# DCSupplyHub.net
KiCad netlist of a schematic drawn in Altium Designer
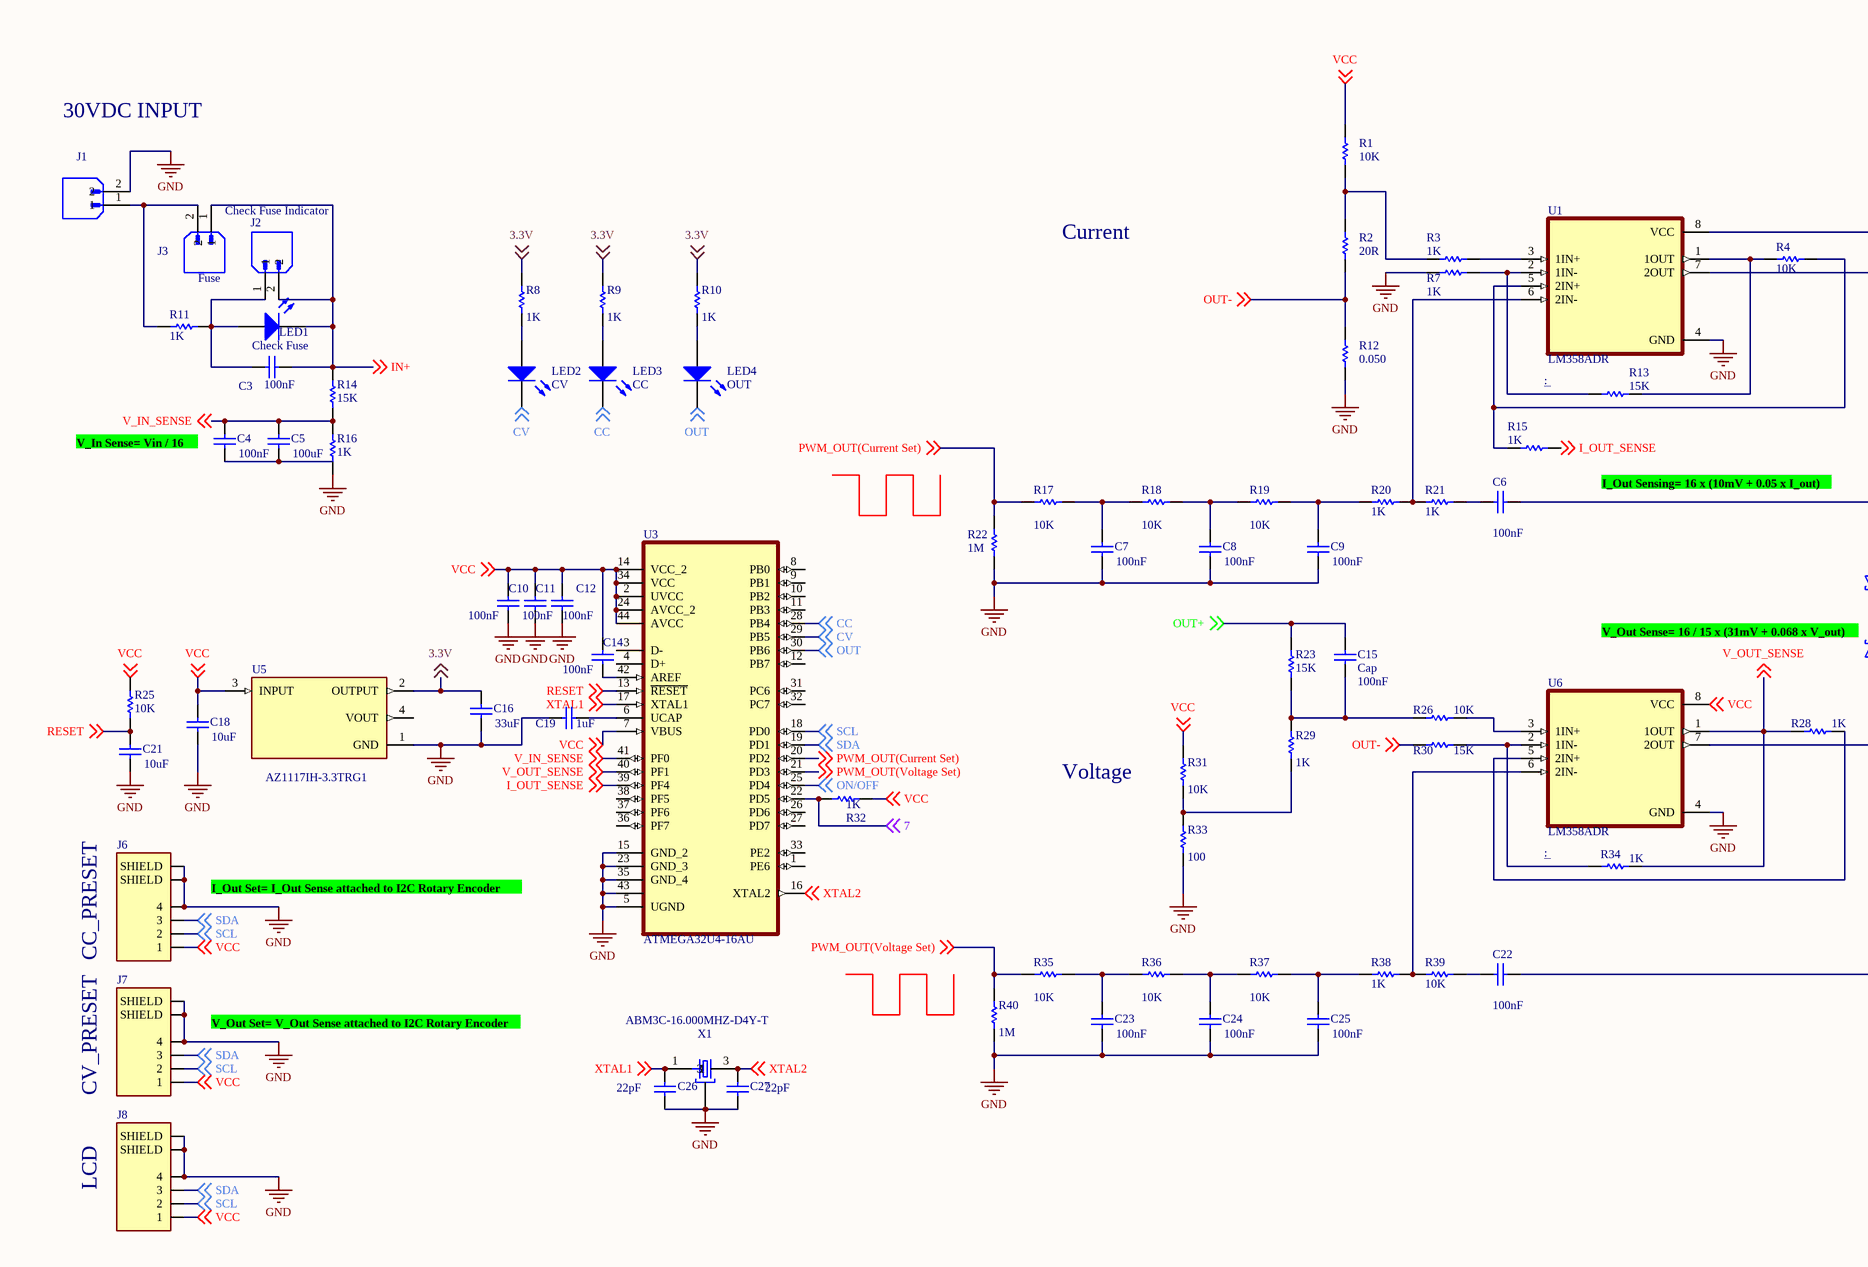
[diagram p0: DCSupplyHub.SchDoc, left]
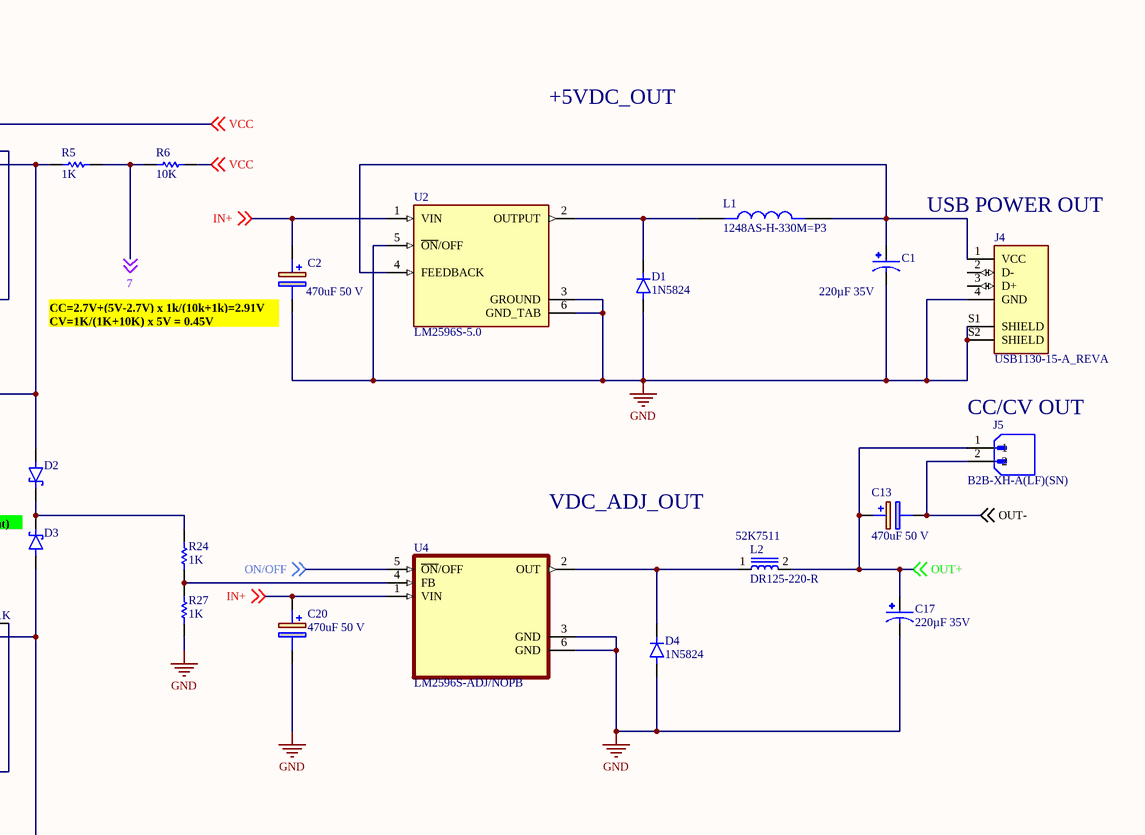
[diagram p1: DCSupplyHub.SchDoc, right]

(export (version "E")
  (design (tool "Eeschema 10.0.6"))
  (components
    (comp (ref "C1")
      (value "EEEFP1V221AP")
      (footprint "CAP_EEEFP1V221AP")
      (description "220ÂµF 35V Aluminum Electrolytic Capacitors Radial, Can - SMD 80mOhm @ 100kHz 2000 Hrs @ 105Â°C")
      (fields
        (field (name "MP") "EEE-FP1V221AP")
        (field (name "MF") "Panasonic Electronic")
        (field (name "PARAMETER 1") "220µF 35V")
      )
      (libsource (lib "cc cv power supply") (part "EEEFP1V221AP"))
    )
    (comp (ref "C2")
      (value "470uF 50 V")
      (footprint "CAPAE1710X1700N")
      (fields
        (field (name "MANUFACTURER_PART_NUMBER") "865060663013")
        (field (name "MOUSER PART NUMBER") "710-865060663013")
      )
      (libsource (lib "cc cv power supply") (part "865060663013"))
    )
    (comp (ref "C3")
      (value "100nF")
      (footprint "CAPC3216X110N")
      (description "Capacitor")
      (fields (field (name "Comment") "Cap") (field (name "PUBLISHER") "Altium Limited"))
      (libsource (lib "cc cv power supply") (part "Cap"))
    )
    (comp (ref "C4")
      (value "100nF")
      (footprint "CAPC3216X110N")
      (description "Capacitor")
      (fields (field (name "Comment") "Cap") (field (name "PUBLISHER") "Altium Limited"))
      (libsource (lib "cc cv power supply") (part "Cap"))
    )
    (comp (ref "C5")
      (value "100uF")
      (footprint "CAPC3216X110N")
      (description "Capacitor")
      (fields (field (name "Comment") "Cap") (field (name "PUBLISHER") "Altium Limited"))
      (libsource (lib "cc cv power supply") (part "Cap"))
    )
    (comp (ref "C6")
      (value "100nF")
      (footprint "CAPC3216X110N")
      (description "Capacitor")
      (fields (field (name "Comment") "Cap") (field (name "PUBLISHER") "Altium Limited"))
      (libsource (lib "cc cv power supply") (part "Cap"))
    )
    (comp (ref "C7")
      (value "100nF")
      (footprint "CAPC3216X110N")
      (description "Capacitor")
      (fields (field (name "Comment") "Cap") (field (name "PUBLISHER") "Altium Limited"))
      (libsource (lib "cc cv power supply") (part "Cap"))
    )
    (comp (ref "C8")
      (value "100nF")
      (footprint "CAPC3216X110N")
      (description "Capacitor")
      (fields (field (name "Comment") "Cap") (field (name "PUBLISHER") "Altium Limited"))
      (libsource (lib "cc cv power supply") (part "Cap"))
    )
    (comp (ref "C9")
      (value "100nF")
      (footprint "CAPC3216X110N")
      (description "Capacitor")
      (fields (field (name "Comment") "Cap") (field (name "PUBLISHER") "Altium Limited"))
      (libsource (lib "cc cv power supply") (part "Cap"))
    )
    (comp (ref "C10")
      (value "100nF")
      (footprint "CAPC3216X110N")
      (description "Capacitor")
      (fields (field (name "Comment") "Cap") (field (name "PUBLISHER") "Altium Limited"))
      (libsource (lib "cc cv power supply") (part "Cap"))
    )
    (comp (ref "C11")
      (value "100nF")
      (footprint "CAPC3216X110N")
      (description "Capacitor")
      (fields (field (name "Comment") "Cap") (field (name "PUBLISHER") "Altium Limited"))
      (libsource (lib "cc cv power supply") (part "Cap"))
    )
    (comp (ref "C12")
      (value "100nF")
      (footprint "CAPC3216X110N")
      (description "Capacitor")
      (fields (field (name "Comment") "Cap") (field (name "PUBLISHER") "Altium Limited"))
      (libsource (lib "cc cv power supply") (part "Cap"))
    )
    (comp (ref "C13")
      (value "470uF 50 V")
      (footprint "CAPAE1710X1700N")
      (fields
        (field (name "MANUFACTURER_PART_NUMBER") "865060663013")
        (field (name "MOUSER PART NUMBER") "710-865060663013")
      )
      (libsource (lib "") (part "865060663013_1"))
    )
    (comp (ref "C14")
      (value "100nF")
      (footprint "CAPC3216X110N")
      (description "Capacitor")
      (fields (field (name "Comment") "Cap") (field (name "PUBLISHER") "Altium Limited"))
      (libsource (lib "Miscellaneous Devices") (part "Cap"))
    )
    (comp (ref "C15")
      (value "Cap")
      (footprint "CAPC3216X110N")
      (description "Capacitor")
      (fields (field (name "ALTIUM_VALUE") "100nF") (field (name "PUBLISHER") "Altium Limited"))
      (libsource (lib "cc cv power supply") (part "Cap"))
    )
    (comp (ref "C16")
      (value "33uF")
      (footprint "CAPC3216X110N")
      (description "Capacitor")
      (fields (field (name "Comment") "Cap") (field (name "PUBLISHER") "Altium Limited"))
      (libsource (lib "cc cv power supply") (part "Cap"))
    )
    (comp (ref "C17")
      (value "EEEFP1V221AP")
      (footprint "CAP_EEEFP1V221AP")
      (description "220ÂµF 35V Aluminum Electrolytic Capacitors Radial, Can - SMD 80mOhm @ 100kHz 2000 Hrs @ 105Â°C")
      (fields
        (field (name "MP") "EEE-FP1V221AP")
        (field (name "MF") "Panasonic Electronic")
        (field (name "PARAMETER 1") "220µF 35V")
      )
      (libsource (lib "cc cv power supply") (part "EEEFP1V221AP"))
    )
    (comp (ref "C18")
      (value "10uF")
      (footprint "CAPC3216X110N")
      (description "Capacitor")
      (fields (field (name "Comment") "Cap") (field (name "PUBLISHER") "Altium Limited"))
      (libsource (lib "cc cv power supply") (part "Cap"))
    )
    (comp (ref "C19")
      (value "1uF")
      (footprint "CAPC3216X110N")
      (description "Capacitor")
      (fields (field (name "Comment") "Cap") (field (name "PUBLISHER") "Altium Limited"))
      (libsource (lib "cc cv power supply") (part "Cap"))
    )
    (comp (ref "C20")
      (value "470uF 50 V")
      (footprint "CAPAE1710X1700N")
      (fields
        (field (name "MANUFACTURER_PART_NUMBER") "865060663013")
        (field (name "MOUSER PART NUMBER") "710-865060663013")
      )
      (libsource (lib "cc cv power supply") (part "865060663013"))
    )
    (comp (ref "C21")
      (value "10uF")
      (footprint "CAPC3216X110N")
      (description "Capacitor")
      (fields (field (name "Comment") "Cap") (field (name "PUBLISHER") "Altium Limited"))
      (libsource (lib "cc cv power supply") (part "Cap"))
    )
    (comp (ref "C22")
      (value "100nF")
      (footprint "CAPC3216X110N")
      (description "Capacitor")
      (fields (field (name "Comment") "Cap") (field (name "PUBLISHER") "Altium Limited"))
      (libsource (lib "cc cv power supply") (part "Cap"))
    )
    (comp (ref "C23")
      (value "100nF")
      (footprint "CAPC3216X110N")
      (description "Capacitor")
      (fields (field (name "Comment") "Cap") (field (name "PUBLISHER") "Altium Limited"))
      (libsource (lib "cc cv power supply") (part "Cap"))
    )
    (comp (ref "C24")
      (value "100nF")
      (footprint "CAPC3216X110N")
      (description "Capacitor")
      (fields (field (name "Comment") "Cap") (field (name "PUBLISHER") "Altium Limited"))
      (libsource (lib "cc cv power supply") (part "Cap"))
    )
    (comp (ref "C25")
      (value "100nF")
      (footprint "CAPC3216X110N")
      (description "Capacitor")
      (fields (field (name "Comment") "Cap") (field (name "PUBLISHER") "Altium Limited"))
      (libsource (lib "cc cv power supply") (part "Cap"))
    )
    (comp (ref "C26")
      (value "22pF")
      (footprint "CAPC3216X110N")
      (description "Capacitor")
      (fields (field (name "Comment") "Cap") (field (name "PUBLISHER") "Altium Limited"))
      (libsource (lib "cc cv power supply") (part "Cap"))
    )
    (comp (ref "C27")
      (value "22pF")
      (footprint "CAPC3216X110N")
      (description "Capacitor")
      (fields (field (name "Comment") "Cap") (field (name "PUBLISHER") "Altium Limited"))
      (libsource (lib "cc cv power supply") (part "Cap"))
    )
    (comp (ref "D1")
      (value "1N5824")
      (footprint "DIOAD1898W129L762D1143")
      (description "Diode Schottky 30V 5A Through Hole Axial")
      (fields (field (name "MF") "Microsemi Corporation"))
      (libsource (lib "cc cv power supply") (part "1N5824"))
    )
    (comp (ref "D2")
      (value "SD1206S020S1R0")
      (footprint "DIOSC190X340X116-2N")
      (description "Diode Schottky 20 V 1A (DC) Surface Mount 1206 (3216 Metric)")
      (fields (field (name "MF") "AVX"))
      (libsource (lib "cc cv power supply") (part "SD1206S020S1R0"))
    )
    (comp (ref "D3")
      (value "SD1206S020S1R0")
      (footprint "DIOSC190X340X116-2N")
      (description "Diode Schottky 20 V 1A (DC) Surface Mount 1206 (3216 Metric)")
      (fields (field (name "MF") "AVX"))
      (libsource (lib "cc cv power supply") (part "SD1206S020S1R0"))
    )
    (comp (ref "D4")
      (value "1N5824")
      (footprint "DIOAD1898W129L762D1143")
      (description "Diode Schottky 30V 5A Through Hole Axial")
      (fields (field (name "MF") "Microsemi Corporation"))
      (libsource (lib "cc cv power supply") (part "1N5824"))
    )
    (comp (ref "J1")
      (value "B2B-XH-A(LF)(SN)")
      (footprint "JST_B2B-XH-A(LF)(SN)")
      (description "Connector Header Through Hole 2 position 0.098 (2.50mm)")
      (fields (field (name "MF") "JST Sales"))
      (libsource (lib "") (part "B2B-XH-A(LF)(SN)_3"))
    )
    (comp (ref "J2")
      (value "Check Fuse Indicator")
      (footprint "JST_B2B-XH-A(LF)(SN)")
      (description "Connector Header Through Hole 2 position 0.098 (2.50mm)")
      (fields (field (name "MF") "JST Sales") (field (name "MP") "B2B-XH-A(LF)(SN)"))
      (libsource (lib "cc cv power supply") (part "B2B-XH-A(LF)(SN)"))
    )
    (comp (ref "J3")
      (value "Fuse")
      (footprint "JST_B2B-XH-A(LF)(SN)")
      (description "Connector Header Through Hole 2 position 0.098 (2.50mm)")
      (fields (field (name "MF") "JST Sales") (field (name "MP") "B2B-XH-A(LF)(SN)"))
      (libsource (lib "") (part "B2B-XH-A(LF)(SN)_2"))
    )
    (comp (ref "J4")
      (value "USB1130-15-A_REVA")
      (footprint "GCT_USB1130-15-A_REVA")
      (fields (field (name "MP") "USB1130-15-A") (field (name "MF") "Global Connector Technology"))
      (libsource (lib "cc cv power supply") (part "USB1130-15-A_REVA"))
    )
    (comp (ref "J5")
      (value "B2B-XH-A(LF)(SN)")
      (footprint "JST_B2B-XH-A(LF)(SN)")
      (description "Connector Header Through Hole 2 position 0.098 (2.50mm)")
      (fields (field (name "MF") "JST Sales"))
      (libsource (lib "") (part "B2B-XH-A(LF)(SN)_1"))
    )
    (comp (ref "J6")
      (value "CC_PRESET")
      (footprint "JST_SM04B-SRSS-TB(LF)(SN)")
      (description "SH Series 1.0 mm Pitch 2 Position Single Row Side Entry Shrouded Header")
      (fields (field (name "MP") "SM04B-SRSS-TB(LF)(SN)"))
      (libsource (lib "cc cv power supply") (part "SM04B-SRSS-TB(LF)(SN)"))
    )
    (comp (ref "J7")
      (value "CV_PRESET")
      (footprint "JST_SM04B-SRSS-TB(LF)(SN)")
      (description "SH Series 1.0 mm Pitch 2 Position Single Row Side Entry Shrouded Header")
      (fields (field (name "MP") "SM04B-SRSS-TB(LF)(SN)"))
      (libsource (lib "cc cv power supply") (part "SM04B-SRSS-TB(LF)(SN)"))
    )
    (comp (ref "J8")
      (value "LCD")
      (footprint "JST_SM04B-SRSS-TB(LF)(SN)")
      (description "SH Series 1.0 mm Pitch 2 Position Single Row Side Entry Shrouded Header")
      (fields (field (name "MP") "SM04B-SRSS-TB(LF)(SN)"))
      (libsource (lib "cc cv power supply") (part "SM04B-SRSS-TB(LF)(SN)"))
    )
    (comp (ref "L1")
      (value "1248AS-H-330M=P3")
      (footprint "IND_1248AS-H-330M=P3")
      (description "Inductor with Inductance: 33uH Tol. +/-20%, Package: 3131 _8080_")
      (fields (field (name "MF") "Murata") (field (name "DIGI-KEY_PART_NUMBER") "490-10797-1-ND"))
      (libsource (lib "cc cv power supply") (part "1248AS-H-330M=P3"))
    )
    (comp (ref "L2")
      (value "DR125-220-R")
      (footprint "INDM1250X1250X600")
      (description "Inductor Power Shielded Drum Core 3.084u(OCL)H/3.3uH 20% 100KHz Ferrite 9.26A 6.3mOhm DCR T/R")
      (fields (field (name "SUPPLIER PART NUMBER 1") "52K7511"))
      (libsource (lib "cc cv power supply") (part "DR125-220-R"))
    )
    (comp (ref "LED1")
      (value "Check Fuse")
      (footprint "3.2X1.6X1.1")
      (description "Typical RED, GREEN, YELLOW, AMBER GaAs LED")
      (fields (field (name "PUBLISHER") "Altium Limited"))
      (libsource (lib "cc cv power supply") (part "LED2"))
    )
    (comp (ref "LED2")
      (value "CV")
      (footprint "3.2X1.6X1.1")
      (description "Typical RED, GREEN, YELLOW, AMBER GaAs LED")
      (fields (field (name "PUBLISHER") "Altium Limited"))
      (libsource (lib "cc cv power supply") (part "LED2"))
    )
    (comp (ref "LED3")
      (value "CC")
      (footprint "3.2X1.6X1.1")
      (description "Typical RED, GREEN, YELLOW, AMBER GaAs LED")
      (fields (field (name "PUBLISHER") "Altium Limited"))
      (libsource (lib "cc cv power supply") (part "LED2"))
    )
    (comp (ref "LED4")
      (value "OUT")
      (footprint "3.2X1.6X1.1")
      (description "Typical RED, GREEN, YELLOW, AMBER GaAs LED")
      (fields (field (name "PUBLISHER") "Altium Limited"))
      (libsource (lib "cc cv power supply") (part "LED2"))
    )
    (comp (ref "R1")
      (value "10K")
      (footprint "RESC3116X60N")
      (description "Resistor")
      (fields (field (name "Comment") "Res1") (field (name "PUBLISHER") "Altium Limited"))
      (libsource (lib "cc cv power supply") (part "Res1"))
    )
    (comp (ref "R2")
      (value "20R")
      (footprint "RESC3116X60N")
      (description "Resistor")
      (fields (field (name "Comment") "Res1") (field (name "PUBLISHER") "Altium Limited"))
      (libsource (lib "cc cv power supply") (part "Res1"))
    )
    (comp (ref "R3")
      (value "1K")
      (footprint "RESC3116X60N")
      (description "Resistor")
      (fields (field (name "Comment") "Res1") (field (name "PUBLISHER") "Altium Limited"))
      (libsource (lib "cc cv power supply") (part "Res1"))
    )
    (comp (ref "R4")
      (value "10K")
      (footprint "RESC3116X60N")
      (description "Resistor")
      (fields (field (name "Comment") "Res1") (field (name "PUBLISHER") "Altium Limited"))
      (libsource (lib "cc cv power supply") (part "Res1"))
    )
    (comp (ref "R5")
      (value "1K")
      (footprint "RESC3116X60N")
      (description "Resistor")
      (fields (field (name "Comment") "Res1") (field (name "PUBLISHER") "Altium Limited"))
      (libsource (lib "cc cv power supply") (part "Res1"))
    )
    (comp (ref "R6")
      (value "10K")
      (footprint "RESC3116X60N")
      (description "Resistor")
      (fields (field (name "Comment") "Res1") (field (name "PUBLISHER") "Altium Limited"))
      (libsource (lib "cc cv power supply") (part "Res1"))
    )
    (comp (ref "R7")
      (value "1K")
      (footprint "RESC3116X60N")
      (description "Resistor")
      (fields (field (name "Comment") "Res1") (field (name "PUBLISHER") "Altium Limited"))
      (libsource (lib "cc cv power supply") (part "Res1"))
    )
    (comp (ref "R8")
      (value "1K")
      (footprint "RESC3116X60N")
      (description "Resistor")
      (fields (field (name "Comment") "Res1") (field (name "PUBLISHER") "Altium Limited"))
      (libsource (lib "cc cv power supply") (part "Res1"))
    )
    (comp (ref "R9")
      (value "1K")
      (footprint "RESC3116X60N")
      (description "Resistor")
      (fields (field (name "Comment") "Res1") (field (name "PUBLISHER") "Altium Limited"))
      (libsource (lib "cc cv power supply") (part "Res1"))
    )
    (comp (ref "R10")
      (value "1K")
      (footprint "RESC3116X60N")
      (description "Resistor")
      (fields (field (name "Comment") "Res1") (field (name "PUBLISHER") "Altium Limited"))
      (libsource (lib "cc cv power supply") (part "Res1"))
    )
    (comp (ref "R11")
      (value "1K")
      (footprint "RESC3116X60N")
      (description "Resistor")
      (fields (field (name "Comment") "Res1") (field (name "PUBLISHER") "Altium Limited"))
      (libsource (lib "cc cv power supply") (part "Res1"))
    )
    (comp (ref "R12")
      (value "0.050")
      (footprint "RESC3116X60N")
      (description "Resistor")
      (fields (field (name "Comment") "Res1") (field (name "PUBLISHER") "Altium Limited"))
      (libsource (lib "cc cv power supply") (part "Res1"))
    )
    (comp (ref "R13")
      (value "15K")
      (footprint "RESC3116X60N")
      (description "Resistor")
      (fields (field (name "Comment") "Res1") (field (name "PUBLISHER") "Altium Limited"))
      (libsource (lib "Miscellaneous Devices") (part "Res1"))
    )
    (comp (ref "R14")
      (value "15K")
      (footprint "RESC3116X60N")
      (description "Resistor")
      (fields (field (name "Comment") "Res1") (field (name "PUBLISHER") "Altium Limited"))
      (libsource (lib "cc cv power supply") (part "Res1"))
    )
    (comp (ref "R15")
      (value "1K")
      (footprint "RESC3116X60N")
      (description "Resistor")
      (fields (field (name "Comment") "Res1") (field (name "PUBLISHER") "Altium Limited"))
      (libsource (lib "cc cv power supply") (part "Res1"))
    )
    (comp (ref "R16")
      (value "1K")
      (footprint "RESC3116X60N")
      (description "Resistor")
      (fields (field (name "Comment") "Res1") (field (name "PUBLISHER") "Altium Limited"))
      (libsource (lib "cc cv power supply") (part "Res1"))
    )
    (comp (ref "R17")
      (value "10K")
      (footprint "RESC3116X60N")
      (description "Resistor")
      (fields (field (name "Comment") "Res1") (field (name "PUBLISHER") "Altium Limited"))
      (libsource (lib "cc cv power supply") (part "Res1"))
    )
    (comp (ref "R18")
      (value "10K")
      (footprint "RESC3116X60N")
      (description "Resistor")
      (fields (field (name "Comment") "Res1") (field (name "PUBLISHER") "Altium Limited"))
      (libsource (lib "cc cv power supply") (part "Res1"))
    )
    (comp (ref "R19")
      (value "10K")
      (footprint "RESC3116X60N")
      (description "Resistor")
      (fields (field (name "Comment") "Res1") (field (name "PUBLISHER") "Altium Limited"))
      (libsource (lib "cc cv power supply") (part "Res1"))
    )
    (comp (ref "R20")
      (value "1K")
      (footprint "RESC3116X60N")
      (description "Resistor")
      (fields (field (name "Comment") "Res1") (field (name "PUBLISHER") "Altium Limited"))
      (libsource (lib "cc cv power supply") (part "Res1"))
    )
    (comp (ref "R21")
      (value "1K")
      (footprint "RESC3116X60N")
      (description "Resistor")
      (fields (field (name "Comment") "Res1") (field (name "PUBLISHER") "Altium Limited"))
      (libsource (lib "cc cv power supply") (part "Res1"))
    )
    (comp (ref "R22")
      (value "1M")
      (footprint "RESC3116X60N")
      (description "Resistor")
      (fields (field (name "Comment") "Res1") (field (name "PUBLISHER") "Altium Limited"))
      (libsource (lib "cc cv power supply") (part "Res1"))
    )
    (comp (ref "R23")
      (value "15K")
      (footprint "RESC3116X60N")
      (description "Resistor")
      (fields (field (name "Comment") "Res1") (field (name "PUBLISHER") "Altium Limited"))
      (libsource (lib "cc cv power supply") (part "Res1"))
    )
    (comp (ref "R24")
      (value "1K")
      (footprint "RESC3116X60N")
      (description "Resistor")
      (fields (field (name "Comment") "Res1") (field (name "PUBLISHER") "Altium Limited"))
      (libsource (lib "cc cv power supply") (part "Res1"))
    )
    (comp (ref "R25")
      (value "10K")
      (footprint "RESC3116X60N")
      (description "Resistor")
      (fields (field (name "Comment") "Res1") (field (name "PUBLISHER") "Altium Limited"))
      (libsource (lib "cc cv power supply") (part "Res1"))
    )
    (comp (ref "R26")
      (value "10K")
      (footprint "RESC3116X60N")
      (description "Resistor")
      (fields (field (name "Comment") "Res1") (field (name "PUBLISHER") "Altium Limited"))
      (libsource (lib "cc cv power supply") (part "Res1"))
    )
    (comp (ref "R27")
      (value "1K")
      (footprint "RESC3116X60N")
      (description "Resistor")
      (fields (field (name "Comment") "Res1") (field (name "PUBLISHER") "Altium Limited"))
      (libsource (lib "cc cv power supply") (part "Res1"))
    )
    (comp (ref "R28")
      (value "1K")
      (footprint "RESC3116X60N")
      (description "Resistor")
      (fields (field (name "Comment") "Res1") (field (name "PUBLISHER") "Altium Limited"))
      (libsource (lib "cc cv power supply") (part "Res1"))
    )
    (comp (ref "R29")
      (value "1K")
      (footprint "RESC3116X60N")
      (description "Resistor")
      (fields (field (name "Comment") "Res1") (field (name "PUBLISHER") "Altium Limited"))
      (libsource (lib "cc cv power supply") (part "Res1"))
    )
    (comp (ref "R30")
      (value "15K")
      (footprint "RESC3116X60N")
      (description "Resistor")
      (fields (field (name "Comment") "Res1") (field (name "PUBLISHER") "Altium Limited"))
      (libsource (lib "cc cv power supply") (part "Res1"))
    )
    (comp (ref "R31")
      (value "10K")
      (footprint "RESC3116X60N")
      (description "Resistor")
      (fields (field (name "Comment") "Res1") (field (name "PUBLISHER") "Altium Limited"))
      (libsource (lib "cc cv power supply") (part "Res1"))
    )
    (comp (ref "R32")
      (value "1K")
      (footprint "RESC3116X60N")
      (description "Resistor")
      (fields (field (name "Comment") "Res1") (field (name "PUBLISHER") "Altium Limited"))
      (libsource (lib "cc cv power supply") (part "Res1"))
    )
    (comp (ref "R33")
      (value "100")
      (footprint "RESC3116X60N")
      (description "Resistor")
      (fields (field (name "Comment") "Res1") (field (name "PUBLISHER") "Altium Limited"))
      (libsource (lib "cc cv power supply") (part "Res1"))
    )
    (comp (ref "R34")
      (value "1K")
      (footprint "RESC3116X60N")
      (description "Resistor")
      (fields (field (name "Comment") "Res1") (field (name "PUBLISHER") "Altium Limited"))
      (libsource (lib "cc cv power supply") (part "Res1"))
    )
    (comp (ref "R35")
      (value "10K")
      (footprint "RESC3116X60N")
      (description "Resistor")
      (fields (field (name "Comment") "Res1") (field (name "PUBLISHER") "Altium Limited"))
      (libsource (lib "cc cv power supply") (part "Res1"))
    )
    (comp (ref "R36")
      (value "10K")
      (footprint "RESC3116X60N")
      (description "Resistor")
      (fields (field (name "Comment") "Res1") (field (name "PUBLISHER") "Altium Limited"))
      (libsource (lib "cc cv power supply") (part "Res1"))
    )
    (comp (ref "R37")
      (value "10K")
      (footprint "RESC3116X60N")
      (description "Resistor")
      (fields (field (name "Comment") "Res1") (field (name "PUBLISHER") "Altium Limited"))
      (libsource (lib "cc cv power supply") (part "Res1"))
    )
    (comp (ref "R38")
      (value "1K")
      (footprint "RESC3116X60N")
      (description "Resistor")
      (fields (field (name "Comment") "Res1") (field (name "PUBLISHER") "Altium Limited"))
      (libsource (lib "cc cv power supply") (part "Res1"))
    )
    (comp (ref "R39")
      (value "10K")
      (footprint "RESC3116X60N")
      (description "Resistor")
      (fields (field (name "Comment") "Res1") (field (name "PUBLISHER") "Altium Limited"))
      (libsource (lib "cc cv power supply") (part "Res1"))
    )
    (comp (ref "R40")
      (value "1M")
      (footprint "RESC3116X60N")
      (description "Resistor")
      (fields (field (name "Comment") "Res1") (field (name "PUBLISHER") "Altium Limited"))
      (libsource (lib "cc cv power supply") (part "Res1"))
    )
    (comp (ref "U1")
      (value "LM358ADR")
      (footprint "SOIC127P599X175-8N")
      (description "Dual improved offset, standard operational amplifier<br /> &nbsp; 8-SOIC 0 to 70")
      (fields (field (name "MF") "Texas Instruments"))
      (libsource (lib "cc cv power supply") (part "LM358ADR"))
    )
    (comp (ref "U2")
      (value "LM2596S-5.0")
      (footprint "TO170P1524X483-6N")
      (description "SIMPLE SWITCHER&reg; 4.5V to 40V, 3A Low Component Count Step-Down Regulator")
      (fields (field (name "MP") "LM2596S-5.0/NOPB") (field (name "MF") "Texas Instruments"))
      (libsource (lib "cc cv power supply") (part "LM2596S-5.0"))
    )
    (comp (ref "U3")
      (value "ATMEGA32U4-16AU")
      (footprint "QFP80P1200X1200X120-44N")
      (description "Microcontroladores de 8 bits - MCU 32K Flash")
      (fields (field (name "MF") "Microchip Technology / Atmel"))
      (libsource (lib "cc cv power supply") (part "ATMEGA32U4-16AU"))
    )
    (comp (ref "U4")
      (value "LM2596S-ADJ/NOPB")
      (footprint "VREG_LM2596S-ADJ/NOPB")
      (description "SIMPLE SWITCHER&reg; 4.5V to 40V, 3A Low Component Count Step-Down Regulator")
      (fields (field (name "MF") "Texas Instruments"))
      (libsource (lib "cc cv power supply") (part "LM2596S-ADJ/NOPB"))
    )
    (comp (ref "U5")
      (value "AZ1117IH-3.3TRG1")
      (footprint "SOT230P700X185-4N")
      (description "Linear Voltage Regulator IC Positive Fixed 1 Output 1A SOT-223-3")
      (fields (field (name "MF") "Diodes Inc."))
      (libsource (lib "cc cv power supply") (part "AZ1117IH-3.3TRG1"))
    )
    (comp (ref "U6")
      (value "LM358ADR")
      (footprint "SOIC127P599X175-8N")
      (description "Dual improved offset, standard operational amplifier<br /> &nbsp; 8-SOIC 0 to 70")
      (fields (field (name "MF") "Texas Instruments"))
      (libsource (lib "cc cv power supply") (part "LM358ADR"))
    )
    (comp (ref "X1")
      (value "ABM3C-16.000MHZ-D4Y-T")
      (footprint "OSCCC500X320X110-4N")
      (description "16MHz Â±30ppm Crystal 18pF 50 Ohms 4-SMD, No Lead")
      (fields (field (name "MF") "Abracon"))
      (libsource (lib "cc cv power supply") (part "ABM3C-16.000MHZ-D4Y-T"))
    )
  )
  (nets
    (net (code "1") (name "3.3V") (class "Default")
      (node (ref "C16") (pin "2") (pinfunction "2_2") (pintype "passive"))
      (node (ref "R10") (pin "1") (pinfunction "1_1") (pintype "passive"))
      (node (ref "R8") (pin "1") (pinfunction "1_1") (pintype "passive"))
      (node (ref "R9") (pin "1") (pinfunction "1_1") (pintype "passive"))
      (node (ref "U5") (pin "2") (pinfunction "OUTPUT_2") (pintype "output"))
    )
    (net (code "2") (name "7") (class "Default")
      (node (ref "R32") (pin "2") (pinfunction "2_2") (pintype "passive"))
      (node (ref "R5") (pin "2") (pinfunction "2_2") (pintype "passive"))
      (node (ref "R6") (pin "1") (pinfunction "1_1") (pintype "passive"))
      (node (ref "U3") (pin "22") (pinfunction "PD5_22") (pintype "bidirectional"))
    )
    (net (code "3") (name "CC") (class "Default")
      (node (ref "LED3") (pin "2") (pinfunction "K_2") (pintype "passive"))
      (node (ref "U3") (pin "28") (pinfunction "PB4_28") (pintype "bidirectional"))
    )
    (net (code "4") (name "CV") (class "Default")
      (node (ref "LED2") (pin "2") (pinfunction "K_2") (pintype "passive"))
      (node (ref "U3") (pin "29") (pinfunction "PB5_29") (pintype "bidirectional"))
    )
    (net (code "5") (name "GND") (class "Default")
      (node (ref "C1") (pin "2") (pinfunction "2_2") (pintype "passive"))
      (node (ref "C10") (pin "1") (pinfunction "1_1") (pintype "passive"))
      (node (ref "C11") (pin "1") (pinfunction "1_1") (pintype "passive"))
      (node (ref "C12") (pin "1") (pinfunction "1_1") (pintype "passive"))
      (node (ref "C16") (pin "1") (pinfunction "1_1") (pintype "passive"))
      (node (ref "C17") (pin "2") (pinfunction "2_2") (pintype "passive"))
      (node (ref "C18") (pin "1") (pinfunction "1_1") (pintype "passive"))
      (node (ref "C19") (pin "2") (pinfunction "2_2") (pintype "passive"))
      (node (ref "C2") (pin "2") (pinfunction "-_2") (pintype "passive"))
      (node (ref "C20") (pin "2") (pinfunction "-_2") (pintype "passive"))
      (node (ref "C21") (pin "1") (pinfunction "1_1") (pintype "passive"))
      (node (ref "C23") (pin "1") (pinfunction "1_1") (pintype "passive"))
      (node (ref "C24") (pin "1") (pinfunction "1_1") (pintype "passive"))
      (node (ref "C25") (pin "1") (pinfunction "1_1") (pintype "passive"))
      (node (ref "C26") (pin "1") (pinfunction "1_1") (pintype "passive"))
      (node (ref "C27") (pin "1") (pinfunction "1_1") (pintype "passive"))
      (node (ref "C7") (pin "1") (pinfunction "1_1") (pintype "passive"))
      (node (ref "C8") (pin "1") (pinfunction "1_1") (pintype "passive"))
      (node (ref "C9") (pin "1") (pinfunction "1_1") (pintype "passive"))
      (node (ref "D1") (pin "A") (pinfunction "A_A") (pintype "passive"))
      (node (ref "D4") (pin "A") (pinfunction "A_A") (pintype "passive"))
      (node (ref "J1") (pin "2") (pinfunction "2_2") (pintype "passive"))
      (node (ref "J4") (pin "4") (pinfunction "GND_4") (pintype "power_in"))
      (node (ref "J4") (pin "S1") (pinfunction "SHIELD_S1") (pintype "passive"))
      (node (ref "J4") (pin "S2") (pinfunction "SHIELD_S2") (pintype "passive"))
      (node (ref "J6") (pin "4") (pinfunction "4_4") (pintype "passive"))
      (node (ref "J6") (pin "S1") (pinfunction "SHIELD_S1") (pintype "passive"))
      (node (ref "J6") (pin "S2") (pinfunction "SHIELD_S2") (pintype "passive"))
      (node (ref "J7") (pin "4") (pinfunction "4_4") (pintype "passive"))
      (node (ref "J7") (pin "S1") (pinfunction "SHIELD_S1") (pintype "passive"))
      (node (ref "J7") (pin "S2") (pinfunction "SHIELD_S2") (pintype "passive"))
      (node (ref "J8") (pin "4") (pinfunction "4_4") (pintype "passive"))
      (node (ref "J8") (pin "S1") (pinfunction "SHIELD_S1") (pintype "passive"))
      (node (ref "J8") (pin "S2") (pinfunction "SHIELD_S2") (pintype "passive"))
      (node (ref "R12") (pin "1") (pinfunction "1_1") (pintype "passive"))
      (node (ref "R16") (pin "2") (pinfunction "2_2") (pintype "passive"))
      (node (ref "R22") (pin "1") (pinfunction "1_1") (pintype "passive"))
      (node (ref "R27") (pin "2") (pinfunction "2_2") (pintype "passive"))
      (node (ref "R33") (pin "1") (pinfunction "1_1") (pintype "passive"))
      (node (ref "R40") (pin "1") (pinfunction "1_1") (pintype "passive"))
      (node (ref "R7") (pin "1") (pinfunction "1_1") (pintype "passive"))
      (node (ref "U1") (pin "4") (pinfunction "GND_4") (pintype "power_in"))
      (node (ref "U2") (pin "3") (pinfunction "GROUND_3") (pintype "power_in"))
      (node (ref "U2") (pin "5") (pinfunction "~{ON}/OFF_5") (pintype "input"))
      (node (ref "U2") (pin "6") (pinfunction "GND_TAB_6") (pintype "power_in"))
      (node (ref "U3") (pin "15") (pinfunction "GND_2_15") (pintype "passive"))
      (node (ref "U3") (pin "23") (pinfunction "GND_3_23") (pintype "passive"))
      (node (ref "U3") (pin "35") (pinfunction "GND_4_35") (pintype "passive"))
      (node (ref "U3") (pin "43") (pinfunction "GND_43") (pintype "passive"))
      (node (ref "U3") (pin "5") (pinfunction "UGND_5") (pintype "passive"))
      (node (ref "U4") (pin "3") (pinfunction "GND_3") (pintype "power_in"))
      (node (ref "U4") (pin "6") (pinfunction "GND_6") (pintype "power_in"))
      (node (ref "U5") (pin "1") (pinfunction "GND_1") (pintype "power_in"))
      (node (ref "U6") (pin "4") (pinfunction "GND_4") (pintype "power_in"))
      (node (ref "X1") (pin "2") (pinfunction "GND_2") (pintype "passive"))
      (node (ref "X1") (pin "4") (pinfunction "GND_4") (pintype "passive"))
    )
    (net (code "6") (name "IN+") (class "Default")
      (node (ref "C2") (pin "1") (pinfunction "+_1") (pintype "passive"))
      (node (ref "C20") (pin "1") (pinfunction "+_1") (pintype "passive"))
      (node (ref "C3") (pin "1") (pinfunction "1_1") (pintype "passive"))
      (node (ref "J2") (pin "2") (pinfunction "2_2") (pintype "passive"))
      (node (ref "J3") (pin "1") (pinfunction "1_1") (pintype "passive"))
      (node (ref "LED1") (pin "2") (pinfunction "K_2") (pintype "passive"))
      (node (ref "R14") (pin "1") (pinfunction "1_1") (pintype "passive"))
      (node (ref "U2") (pin "1") (pinfunction "VIN_1") (pintype "input"))
      (node (ref "U4") (pin "1") (pinfunction "VIN_1") (pintype "input"))
    )
    (net (code "7") (name "I_OUT_SENSE") (class "Default")
      (node (ref "R15") (pin "1") (pinfunction "1_1") (pintype "passive"))
      (node (ref "U3") (pin "39") (pinfunction "PF4_39") (pintype "bidirectional"))
    )
    (net (code "8") (name "Net-(C4-Pad1)") (class "Default")
      (node (ref "C4") (pin "1") (pinfunction "1_1") (pintype "passive"))
      (node (ref "C5") (pin "1") (pinfunction "1_1") (pintype "passive"))
    )
    (net (code "9") (name "Net-(C6-Pad1)") (class "Default")
      (node (ref "C6") (pin "1") (pinfunction "1_1") (pintype "passive"))
      (node (ref "R21") (pin "2") (pinfunction "2_2") (pintype "passive"))
    )
    (net (code "10") (name "Net-(C7-Pad2)") (class "Default")
      (node (ref "C7") (pin "2") (pinfunction "2_2") (pintype "passive"))
      (node (ref "R17") (pin "1") (pinfunction "1_1") (pintype "passive"))
      (node (ref "R18") (pin "2") (pinfunction "2_2") (pintype "passive"))
    )
    (net (code "11") (name "Net-(C8-Pad2)") (class "Default")
      (node (ref "C8") (pin "2") (pinfunction "2_2") (pintype "passive"))
      (node (ref "R18") (pin "1") (pinfunction "1_1") (pintype "passive"))
      (node (ref "R19") (pin "2") (pinfunction "2_2") (pintype "passive"))
    )
    (net (code "12") (name "Net-(C9-Pad2)") (class "Default")
      (node (ref "C9") (pin "2") (pinfunction "2_2") (pintype "passive"))
      (node (ref "R19") (pin "1") (pinfunction "1_1") (pintype "passive"))
      (node (ref "R20") (pin "1") (pinfunction "1_1") (pintype "passive"))
    )
    (net (code "13") (name "Net-(C15-Pad2)") (class "Default")
      (node (ref "C15") (pin "2") (pinfunction "2_2") (pintype "passive"))
      (node (ref "R23") (pin "1") (pinfunction "1_1") (pintype "passive"))
      (node (ref "R26") (pin "1") (pinfunction "1_1") (pintype "passive"))
      (node (ref "R29") (pin "1") (pinfunction "1_1") (pintype "passive"))
    )
    (net (code "14") (name "Net-(C22-Pad1)") (class "Default")
      (node (ref "C22") (pin "1") (pinfunction "1_1") (pintype "passive"))
      (node (ref "R39") (pin "2") (pinfunction "2_2") (pintype "passive"))
    )
    (net (code "15") (name "Net-(C23-Pad2)") (class "Default")
      (node (ref "C23") (pin "2") (pinfunction "2_2") (pintype "passive"))
      (node (ref "R35") (pin "1") (pinfunction "1_1") (pintype "passive"))
      (node (ref "R36") (pin "2") (pinfunction "2_2") (pintype "passive"))
    )
    (net (code "16") (name "Net-(C24-Pad2)") (class "Default")
      (node (ref "C24") (pin "2") (pinfunction "2_2") (pintype "passive"))
      (node (ref "R36") (pin "1") (pinfunction "1_1") (pintype "passive"))
      (node (ref "R37") (pin "2") (pinfunction "2_2") (pintype "passive"))
    )
    (net (code "17") (name "Net-(C25-Pad2)") (class "Default")
      (node (ref "C25") (pin "2") (pinfunction "2_2") (pintype "passive"))
      (node (ref "R37") (pin "1") (pinfunction "1_1") (pintype "passive"))
      (node (ref "R38") (pin "1") (pinfunction "1_1") (pintype "passive"))
    )
    (net (code "18") (name "Net-(D1-K)") (class "Default")
      (node (ref "D1") (pin "C") (pinfunction "K_C") (pintype "passive"))
      (node (ref "L1") (pin "1") (pinfunction "1_1") (pintype "passive"))
      (node (ref "U2") (pin "2") (pinfunction "OUTPUT_2") (pintype "output"))
    )
    (net (code "19") (name "Net-(D2-K)") (class "Default")
      (node (ref "D2") (pin "C") (pinfunction "K_C") (pintype "passive"))
      (node (ref "D3") (pin "C") (pinfunction "K_C") (pintype "passive"))
      (node (ref "R24") (pin "1") (pinfunction "1_1") (pintype "passive"))
    )
    (net (code "20") (name "Net-(D4-K)") (class "Default")
      (node (ref "D4") (pin "C") (pinfunction "K_C") (pintype "passive"))
      (node (ref "L2") (pin "1") (pinfunction "1_1") (pintype "passive"))
      (node (ref "U4") (pin "2") (pinfunction "OUT_2") (pintype "output"))
    )
    (net (code "21") (name "Net-(J1-Pad1)") (class "Default")
      (node (ref "J1") (pin "1") (pinfunction "1_1") (pintype "passive"))
      (node (ref "J3") (pin "2") (pinfunction "2_2") (pintype "passive"))
      (node (ref "R11") (pin "1") (pinfunction "1_1") (pintype "passive"))
    )
    (net (code "22") (name "Net-(J4-VCC)") (class "Default")
      (node (ref "C1") (pin "1") (pinfunction "1_1") (pintype "passive"))
      (node (ref "J4") (pin "1") (pinfunction "VCC_1") (pintype "power_in"))
      (node (ref "L1") (pin "2") (pinfunction "2_2") (pintype "passive"))
      (node (ref "U2") (pin "4") (pinfunction "FEEDBACK_4") (pintype "input"))
    )
    (net (code "23") (name "Net-(LED1-A)") (class "Default")
      (node (ref "C3") (pin "2") (pinfunction "2_2") (pintype "passive"))
      (node (ref "J2") (pin "1") (pinfunction "1_1") (pintype "passive"))
      (node (ref "LED1") (pin "1") (pinfunction "A_1") (pintype "passive"))
      (node (ref "R11") (pin "2") (pinfunction "2_2") (pintype "passive"))
    )
    (net (code "24") (name "Net-(LED2-A)") (class "Default")
      (node (ref "LED2") (pin "1") (pinfunction "A_1") (pintype "passive"))
      (node (ref "R8") (pin "2") (pinfunction "2_2") (pintype "passive"))
    )
    (net (code "25") (name "Net-(LED3-A)") (class "Default")
      (node (ref "LED3") (pin "1") (pinfunction "A_1") (pintype "passive"))
      (node (ref "R9") (pin "2") (pinfunction "2_2") (pintype "passive"))
    )
    (net (code "26") (name "Net-(LED4-A)") (class "Default")
      (node (ref "LED4") (pin "1") (pinfunction "A_1") (pintype "passive"))
      (node (ref "R10") (pin "2") (pinfunction "2_2") (pintype "passive"))
    )
    (net (code "27") (name "Net-(R1-Pad1)") (class "Default")
      (node (ref "R1") (pin "1") (pinfunction "1_1") (pintype "passive"))
      (node (ref "R2") (pin "1") (pinfunction "1_1") (pintype "passive"))
      (node (ref "R3") (pin "1") (pinfunction "1_1") (pintype "passive"))
    )
    (net (code "28") (name "Net-(R29-Pad2)") (class "Default")
      (node (ref "R29") (pin "2") (pinfunction "2_2") (pintype "passive"))
      (node (ref "R31") (pin "2") (pinfunction "2_2") (pintype "passive"))
      (node (ref "R33") (pin "2") (pinfunction "2_2") (pintype "passive"))
    )
    (net (code "29") (name "Net-(U1-1IN+)") (class "Default")
      (node (ref "R3") (pin "2") (pinfunction "2_2") (pintype "passive"))
      (node (ref "U1") (pin "3") (pinfunction "1IN+_3") (pintype "input"))
    )
    (net (code "30") (name "Net-(U1-1IN-)") (class "Default")
      (node (ref "R13") (pin "1") (pinfunction "1_1") (pintype "passive"))
      (node (ref "R7") (pin "2") (pinfunction "2_2") (pintype "passive"))
      (node (ref "U1") (pin "2") (pinfunction "1IN-_2") (pintype "input"))
    )
    (net (code "31") (name "Net-(U1-1OUT)") (class "Default")
      (node (ref "R13") (pin "2") (pinfunction "2_2") (pintype "passive"))
      (node (ref "R4") (pin "1") (pinfunction "1_1") (pintype "passive"))
      (node (ref "U1") (pin "1") (pinfunction "1OUT_1") (pintype "output"))
    )
    (net (code "32") (name "Net-(U1-2IN+)") (class "Default")
      (node (ref "R15") (pin "2") (pinfunction "2_2") (pintype "passive"))
      (node (ref "R4") (pin "2") (pinfunction "2_2") (pintype "passive"))
      (node (ref "U1") (pin "5") (pinfunction "2IN+_5") (pintype "input"))
    )
    (net (code "33") (name "Net-(U1-2IN-)") (class "Default")
      (node (ref "R20") (pin "2") (pinfunction "2_2") (pintype "passive"))
      (node (ref "R21") (pin "1") (pinfunction "1_1") (pintype "passive"))
      (node (ref "U1") (pin "6") (pinfunction "2IN-_6") (pintype "input"))
    )
    (net (code "34") (name "Net-(U1-2OUT)") (class "Default")
      (node (ref "C6") (pin "2") (pinfunction "2_2") (pintype "passive"))
      (node (ref "D2") (pin "A") (pinfunction "A_A") (pintype "passive"))
      (node (ref "R5") (pin "1") (pinfunction "1_1") (pintype "passive"))
      (node (ref "U1") (pin "7") (pinfunction "2OUT_7") (pintype "output"))
    )
    (net (code "35") (name "Net-(U3-AREF)") (class "Default")
      (node (ref "C14") (pin "1") (pinfunction "1_1") (pintype "passive"))
      (node (ref "U3") (pin "42") (pinfunction "AREF_42") (pintype "input"))
    )
    (net (code "36") (name "Net-(U3-UCAP)") (class "Default")
      (node (ref "C19") (pin "1") (pinfunction "1_1") (pintype "passive"))
      (node (ref "U3") (pin "6") (pinfunction "UCAP_6") (pintype "power_in"))
    )
    (net (code "37") (name "Net-(U4-FB)") (class "Default")
      (node (ref "R24") (pin "2") (pinfunction "2_2") (pintype "passive"))
      (node (ref "R27") (pin "1") (pinfunction "1_1") (pintype "passive"))
      (node (ref "U4") (pin "4") (pinfunction "FB_4") (pintype "input"))
    )
    (net (code "38") (name "Net-(U6-1IN+)") (class "Default")
      (node (ref "R26") (pin "2") (pinfunction "2_2") (pintype "passive"))
      (node (ref "U6") (pin "3") (pinfunction "1IN+_3") (pintype "input"))
    )
    (net (code "39") (name "Net-(U6-1IN-)") (class "Default")
      (node (ref "R30") (pin "2") (pinfunction "2_2") (pintype "passive"))
      (node (ref "R34") (pin "1") (pinfunction "1_1") (pintype "passive"))
      (node (ref "U6") (pin "2") (pinfunction "1IN-_2") (pintype "input"))
    )
    (net (code "40") (name "Net-(U6-2IN+)") (class "Default")
      (node (ref "R28") (pin "2") (pinfunction "2_2") (pintype "passive"))
      (node (ref "U6") (pin "5") (pinfunction "2IN+_5") (pintype "input"))
    )
    (net (code "41") (name "Net-(U6-2IN-)") (class "Default")
      (node (ref "R38") (pin "2") (pinfunction "2_2") (pintype "passive"))
      (node (ref "R39") (pin "1") (pinfunction "1_1") (pintype "passive"))
      (node (ref "U6") (pin "6") (pinfunction "2IN-_6") (pintype "input"))
    )
    (net (code "42") (name "Net-(U6-2OUT)") (class "Default")
      (node (ref "C22") (pin "2") (pinfunction "2_2") (pintype "passive"))
      (node (ref "D3") (pin "A") (pinfunction "A_A") (pintype "passive"))
      (node (ref "U6") (pin "7") (pinfunction "2OUT_7") (pintype "output"))
    )
    (net (code "43") (name "ON{slash}OFF") (class "Default")
      (node (ref "U3") (pin "25") (pinfunction "PD4_25") (pintype "bidirectional"))
      (node (ref "U4") (pin "5") (pinfunction "~{ON}/OFF_5") (pintype "input"))
    )
    (net (code "44") (name "OUT") (class "Default")
      (node (ref "LED4") (pin "2") (pinfunction "K_2") (pintype "passive"))
      (node (ref "U3") (pin "30") (pinfunction "PB6_30") (pintype "bidirectional"))
    )
    (net (code "45") (name "OUT+") (class "Default")
      (node (ref "C13") (pin "1") (pinfunction "+_1") (pintype "passive"))
      (node (ref "C15") (pin "1") (pinfunction "1_1") (pintype "passive"))
      (node (ref "C17") (pin "1") (pinfunction "1_1") (pintype "passive"))
      (node (ref "J5") (pin "1") (pinfunction "1_1") (pintype "passive"))
      (node (ref "L2") (pin "2") (pinfunction "2_2") (pintype "passive"))
      (node (ref "R23") (pin "2") (pinfunction "2_2") (pintype "passive"))
    )
    (net (code "46") (name "OUT-") (class "Default")
      (node (ref "C13") (pin "2") (pinfunction "-_2") (pintype "passive"))
      (node (ref "J5") (pin "2") (pinfunction "2_2") (pintype "passive"))
      (node (ref "R12") (pin "2") (pinfunction "2_2") (pintype "passive"))
      (node (ref "R2") (pin "2") (pinfunction "2_2") (pintype "passive"))
      (node (ref "R30") (pin "1") (pinfunction "1_1") (pintype "passive"))
    )
    (net (code "47") (name "PWM_OUT(Current Set)") (class "Default")
      (node (ref "R17") (pin "2") (pinfunction "2_2") (pintype "passive"))
      (node (ref "R22") (pin "2") (pinfunction "2_2") (pintype "passive"))
      (node (ref "U3") (pin "20") (pinfunction "PD2_20") (pintype "bidirectional"))
    )
    (net (code "48") (name "PWM_OUT(Voltage Set)") (class "Default")
      (node (ref "R35") (pin "2") (pinfunction "2_2") (pintype "passive"))
      (node (ref "R40") (pin "2") (pinfunction "2_2") (pintype "passive"))
      (node (ref "U3") (pin "21") (pinfunction "PD3_21") (pintype "bidirectional"))
    )
    (net (code "49") (name "RESET") (class "Default")
      (node (ref "C21") (pin "2") (pinfunction "2_2") (pintype "passive"))
      (node (ref "R25") (pin "2") (pinfunction "2_2") (pintype "passive"))
      (node (ref "U3") (pin "13") (pinfunction "~{RESET}_13") (pintype "input"))
    )
    (net (code "50") (name "SCL") (class "Default")
      (node (ref "J6") (pin "2") (pinfunction "2_2") (pintype "passive"))
      (node (ref "J7") (pin "2") (pinfunction "2_2") (pintype "passive"))
      (node (ref "J8") (pin "2") (pinfunction "2_2") (pintype "passive"))
      (node (ref "U3") (pin "18") (pinfunction "PD0_18") (pintype "bidirectional"))
    )
    (net (code "51") (name "SDA") (class "Default")
      (node (ref "J6") (pin "3") (pinfunction "3_3") (pintype "passive"))
      (node (ref "J7") (pin "3") (pinfunction "3_3") (pintype "passive"))
      (node (ref "J8") (pin "3") (pinfunction "3_3") (pintype "passive"))
      (node (ref "U3") (pin "19") (pinfunction "PD1_19") (pintype "bidirectional"))
    )
    (net (code "52") (name "VCC") (class "Default")
      (node (ref "C10") (pin "2") (pinfunction "2_2") (pintype "passive"))
      (node (ref "C11") (pin "2") (pinfunction "2_2") (pintype "passive"))
      (node (ref "C12") (pin "2") (pinfunction "2_2") (pintype "passive"))
      (node (ref "C14") (pin "2") (pinfunction "2_2") (pintype "passive"))
      (node (ref "C18") (pin "2") (pinfunction "2_2") (pintype "passive"))
      (node (ref "J6") (pin "1") (pinfunction "1_1") (pintype "passive"))
      (node (ref "J7") (pin "1") (pinfunction "1_1") (pintype "passive"))
      (node (ref "J8") (pin "1") (pinfunction "1_1") (pintype "passive"))
      (node (ref "R1") (pin "2") (pinfunction "2_2") (pintype "passive"))
      (node (ref "R25") (pin "1") (pinfunction "1_1") (pintype "passive"))
      (node (ref "R31") (pin "1") (pinfunction "1_1") (pintype "passive"))
      (node (ref "R32") (pin "1") (pinfunction "1_1") (pintype "passive"))
      (node (ref "R6") (pin "2") (pinfunction "2_2") (pintype "passive"))
      (node (ref "U1") (pin "8") (pinfunction "VCC_8") (pintype "power_in"))
      (node (ref "U3") (pin "14") (pinfunction "VCC_2_14") (pintype "power_in"))
      (node (ref "U3") (pin "2") (pinfunction "UVCC_2") (pintype "power_in"))
      (node (ref "U3") (pin "24") (pinfunction "AVCC_2_24") (pintype "power_in"))
      (node (ref "U3") (pin "34") (pinfunction "VCC_34") (pintype "power_in"))
      (node (ref "U3") (pin "44") (pinfunction "AVCC_44") (pintype "power_in"))
      (node (ref "U3") (pin "7") (pinfunction "VBUS_7") (pintype "input"))
      (node (ref "U5") (pin "3") (pinfunction "INPUT_3") (pintype "input"))
      (node (ref "U6") (pin "8") (pinfunction "VCC_8") (pintype "power_in"))
    )
    (net (code "53") (name "V_IN_SENSE") (class "Default")
      (node (ref "C4") (pin "2") (pinfunction "2_2") (pintype "passive"))
      (node (ref "C5") (pin "2") (pinfunction "2_2") (pintype "passive"))
      (node (ref "R14") (pin "2") (pinfunction "2_2") (pintype "passive"))
      (node (ref "R16") (pin "1") (pinfunction "1_1") (pintype "passive"))
      (node (ref "U3") (pin "41") (pinfunction "PF0_41") (pintype "bidirectional"))
    )
    (net (code "54") (name "V_OUT_SENSE") (class "Default")
      (node (ref "R28") (pin "1") (pinfunction "1_1") (pintype "passive"))
      (node (ref "R34") (pin "2") (pinfunction "2_2") (pintype "passive"))
      (node (ref "U3") (pin "40") (pinfunction "PF1_40") (pintype "bidirectional"))
      (node (ref "U6") (pin "1") (pinfunction "1OUT_1") (pintype "output"))
    )
    (net (code "55") (name "XTAL1") (class "Default")
      (node (ref "C26") (pin "2") (pinfunction "2_2") (pintype "passive"))
      (node (ref "U3") (pin "17") (pinfunction "XTAL1_17") (pintype "input"))
      (node (ref "X1") (pin "1") (pinfunction "1_1") (pintype "passive"))
    )
    (net (code "56") (name "XTAL2") (class "Default")
      (node (ref "C27") (pin "2") (pinfunction "2_2") (pintype "passive"))
      (node (ref "U3") (pin "16") (pinfunction "XTAL2_16") (pintype "output"))
      (node (ref "X1") (pin "3") (pinfunction "3_3") (pintype "passive"))
    )
    (net (code "57") (name "unconnected-(J4-D+-Pad3)") (class "Default")
      (node (ref "J4") (pin "3") (pinfunction "D+_3") (pintype "bidirectional"))
    )
    (net (code "58") (name "unconnected-(J4-D--Pad2)") (class "Default")
      (node (ref "J4") (pin "2") (pinfunction "D-_2") (pintype "bidirectional"))
    )
    (net (code "59") (name "unconnected-(U3-D+-Pad4)") (class "Default")
      (node (ref "U3") (pin "4") (pinfunction "D+_4") (pintype "passive"))
    )
    (net (code "60") (name "unconnected-(U3-D--Pad3)") (class "Default")
      (node (ref "U3") (pin "3") (pinfunction "D-_3") (pintype "passive"))
    )
    (net (code "61") (name "unconnected-(U3-PB0-Pad8)") (class "Default")
      (node (ref "U3") (pin "8") (pinfunction "PB0_8") (pintype "bidirectional"))
    )
    (net (code "62") (name "unconnected-(U3-PB1-Pad9)") (class "Default")
      (node (ref "U3") (pin "9") (pinfunction "PB1_9") (pintype "bidirectional"))
    )
    (net (code "63") (name "unconnected-(U3-PB2-Pad10)") (class "Default")
      (node (ref "U3") (pin "10") (pinfunction "PB2_10") (pintype "bidirectional"))
    )
    (net (code "64") (name "unconnected-(U3-PB3-Pad11)") (class "Default")
      (node (ref "U3") (pin "11") (pinfunction "PB3_11") (pintype "bidirectional"))
    )
    (net (code "65") (name "unconnected-(U3-PB7-Pad12)") (class "Default")
      (node (ref "U3") (pin "12") (pinfunction "PB7_12") (pintype "bidirectional"))
    )
    (net (code "66") (name "unconnected-(U3-PC6-Pad31)") (class "Default")
      (node (ref "U3") (pin "31") (pinfunction "PC6_31") (pintype "bidirectional"))
    )
    (net (code "67") (name "unconnected-(U3-PC7-Pad32)") (class "Default")
      (node (ref "U3") (pin "32") (pinfunction "PC7_32") (pintype "bidirectional"))
    )
    (net (code "68") (name "unconnected-(U3-PD6-Pad26)") (class "Default")
      (node (ref "U3") (pin "26") (pinfunction "PD6_26") (pintype "bidirectional"))
    )
    (net (code "69") (name "unconnected-(U3-PD7-Pad27)") (class "Default")
      (node (ref "U3") (pin "27") (pinfunction "PD7_27") (pintype "bidirectional"))
    )
    (net (code "70") (name "unconnected-(U3-PE2-Pad33)") (class "Default")
      (node (ref "U3") (pin "33") (pinfunction "PE2_33") (pintype "bidirectional"))
    )
    (net (code "71") (name "unconnected-(U3-PE6-Pad1)") (class "Default")
      (node (ref "U3") (pin "1") (pinfunction "PE6_1") (pintype "bidirectional"))
    )
    (net (code "72") (name "unconnected-(U3-PF5-Pad38)") (class "Default")
      (node (ref "U3") (pin "38") (pinfunction "PF5_38") (pintype "bidirectional"))
    )
    (net (code "73") (name "unconnected-(U3-PF6-Pad37)") (class "Default")
      (node (ref "U3") (pin "37") (pinfunction "PF6_37") (pintype "bidirectional"))
    )
    (net (code "74") (name "unconnected-(U3-PF7-Pad36)") (class "Default")
      (node (ref "U3") (pin "36") (pinfunction "PF7_36") (pintype "bidirectional"))
    )
    (net (code "75") (name "unconnected-(U5-VOUT-Pad4)") (class "Default")
      (node (ref "U5") (pin "4") (pinfunction "VOUT_4") (pintype "output"))
    )
  )
)
